# OpenRing_Touch.net
KiCad netlist of a schematic drawn in Altium Designer
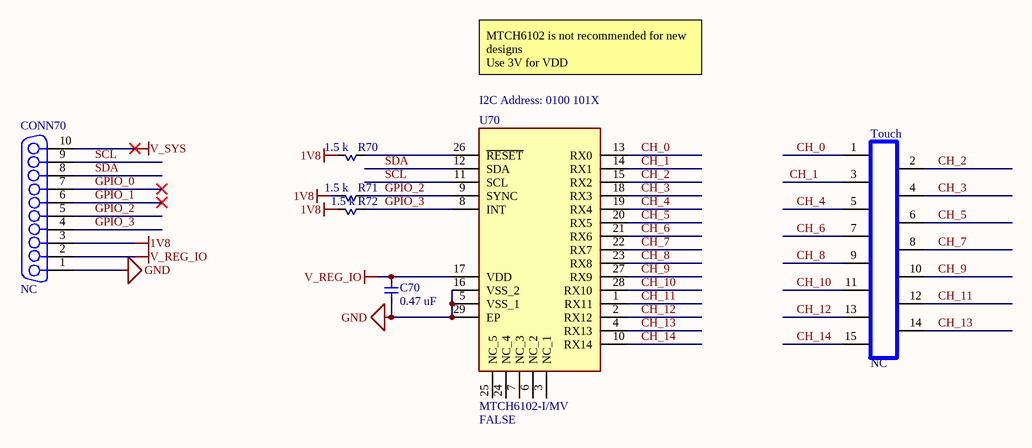
[diagram p0: OpenRing_Touch.SchDoc]

(export (version "E")
  (design (tool "Eeschema 10.0.6"))
  (components
    (comp (ref "C70")
      (value "0.47 uF")
      (footprint "CAPC1005X05N")
      (description "CAP CER 0.47UF 10V X5R 0402")
      (fields
        (field (name "MANUFACTURER") "Murata Electronics North America")
        (field (name "MANUFACTURER PART NUMBER") "GRM155R61A474KE15D")
      )
      (libsource (lib "OpenRingComponents") (part "GRM155R61A474KE15D"))
    )
    (comp (ref "CONN70")
      (value "NC")
      (footprint "51281-1098-PCB")
      (libsource (lib "Connectors") (part "51281-1098-PCB"))
    )
    (comp (ref "R70")
      (value "1.5 k")
      (footprint "RESC1005X04N")
      (description "RES SMD 1.5K OHM 1% 1/10W 0402")
      (fields
        (field (name "MANUFACTURER") "Panasonic Electronic Components")
        (field (name "MANUFACTURER PART NUMBER") "ERJ-2RKF1501X")
      )
      (libsource (lib "OpenRingComponents") (part "ERJ-2RKF1501X"))
    )
    (comp (ref "R71")
      (value "1.5 k")
      (footprint "RESC1005X04N")
      (description "RES SMD 1.5K OHM 1% 1/10W 0402")
      (fields
        (field (name "MANUFACTURER") "Panasonic Electronic Components")
        (field (name "MANUFACTURER PART NUMBER") "ERJ-2RKF1501X")
      )
      (libsource (lib "OpenRingComponents") (part "ERJ-2RKF1501X"))
    )
    (comp (ref "R72")
      (value "1.5 k")
      (footprint "RESC1005X04N")
      (description "RES SMD 1.5K OHM 1% 1/10W 0402")
      (fields
        (field (name "MANUFACTURER") "Panasonic Electronic Components")
        (field (name "MANUFACTURER PART NUMBER") "ERJ-2RKF1501X")
      )
      (libsource (lib "OpenRingComponents") (part "ERJ-2RKF1501X"))
    )
    (comp (ref "Touch")
      (value "NC")
      (footprint "Touch-15Ch-Linear")
      (libsource (lib "OpenRingComponents") (part "Touch-15Ch-Linear"))
    )
    (comp (ref "U70")
      (value "MTCH6102-I/MV")
      (footprint "QFN40P400X400X55_HS-29N")
      (description "Capacitive Touch Screen Automotive 28-Pin UQFN EP Tube")
      (fields (field (name "MANUFACTURER") "Microchip") (field (name "CHECKED") "FALSE"))
      (libsource (lib "OpenRingComponents") (part "MTCH6102-I/MV"))
    )
  )
  (nets
    (net (code "1") (name "/CH_0") (class "Default")
      (node (ref "Touch") (pin "1") (pinfunction "1_1") (pintype "passive"))
      (node (ref "U70") (pin "13") (pinfunction "RX0_13") (pintype "passive"))
    )
    (net (code "2") (name "/CH_1") (class "Default")
      (node (ref "Touch") (pin "3") (pinfunction "3_3") (pintype "passive"))
      (node (ref "U70") (pin "14") (pinfunction "RX1_14") (pintype "passive"))
    )
    (net (code "3") (name "/CH_2") (class "Default")
      (node (ref "Touch") (pin "2") (pinfunction "2_2") (pintype "passive"))
      (node (ref "U70") (pin "15") (pinfunction "RX2_15") (pintype "passive"))
    )
    (net (code "4") (name "/CH_3") (class "Default")
      (node (ref "Touch") (pin "4") (pinfunction "4_4") (pintype "passive"))
      (node (ref "U70") (pin "18") (pinfunction "RX3_18") (pintype "passive"))
    )
    (net (code "5") (name "/CH_4") (class "Default")
      (node (ref "Touch") (pin "5") (pinfunction "5_5") (pintype "passive"))
      (node (ref "U70") (pin "19") (pinfunction "RX4_19") (pintype "passive"))
    )
    (net (code "6") (name "/CH_5") (class "Default")
      (node (ref "Touch") (pin "6") (pinfunction "6_6") (pintype "passive"))
      (node (ref "U70") (pin "20") (pinfunction "RX5_20") (pintype "passive"))
    )
    (net (code "7") (name "/CH_6") (class "Default")
      (node (ref "Touch") (pin "7") (pinfunction "7_7") (pintype "passive"))
      (node (ref "U70") (pin "21") (pinfunction "RX6_21") (pintype "passive"))
    )
    (net (code "8") (name "/CH_7") (class "Default")
      (node (ref "Touch") (pin "8") (pinfunction "8_8") (pintype "passive"))
      (node (ref "U70") (pin "22") (pinfunction "RX7_22") (pintype "passive"))
    )
    (net (code "9") (name "/CH_8") (class "Default")
      (node (ref "Touch") (pin "9") (pinfunction "9_9") (pintype "passive"))
      (node (ref "U70") (pin "23") (pinfunction "RX8_23") (pintype "passive"))
    )
    (net (code "10") (name "/CH_9") (class "Default")
      (node (ref "Touch") (pin "10") (pinfunction "10_10") (pintype "passive"))
      (node (ref "U70") (pin "27") (pinfunction "RX9_27") (pintype "passive"))
    )
    (net (code "11") (name "/CH_10") (class "Default")
      (node (ref "Touch") (pin "11") (pinfunction "11_11") (pintype "passive"))
      (node (ref "U70") (pin "28") (pinfunction "RX10_28") (pintype "passive"))
    )
    (net (code "12") (name "/CH_11") (class "Default")
      (node (ref "Touch") (pin "12") (pinfunction "12_12") (pintype "passive"))
      (node (ref "U70") (pin "1") (pinfunction "RX11_1") (pintype "passive"))
    )
    (net (code "13") (name "/CH_12") (class "Default")
      (node (ref "Touch") (pin "13") (pinfunction "13_13") (pintype "passive"))
      (node (ref "U70") (pin "2") (pinfunction "RX12_2") (pintype "passive"))
    )
    (net (code "14") (name "/CH_13") (class "Default")
      (node (ref "Touch") (pin "14") (pinfunction "14_14") (pintype "passive"))
      (node (ref "U70") (pin "4") (pinfunction "RX13_4") (pintype "passive"))
    )
    (net (code "15") (name "/CH_14") (class "Default")
      (node (ref "Touch") (pin "15") (pinfunction "15_15") (pintype "passive"))
      (node (ref "U70") (pin "10") (pinfunction "RX14_10") (pintype "passive"))
    )
    (net (code "16") (name "/GPIO_0") (class "Default")
      (node (ref "CONN70") (pin "7") (pinfunction "7_7") (pintype "passive+no_connect"))
    )
    (net (code "17") (name "/GPIO_1") (class "Default")
      (node (ref "CONN70") (pin "6") (pinfunction "6_6") (pintype "passive+no_connect"))
    )
    (net (code "18") (name "/GPIO_2") (class "Default")
      (node (ref "CONN70") (pin "5") (pinfunction "5_5") (pintype "passive"))
      (node (ref "R71") (pin "1") (pinfunction "1_1") (pintype "passive"))
      (node (ref "U70") (pin "9") (pinfunction "SYNC_9") (pintype "passive"))
    )
    (net (code "19") (name "/GPIO_3") (class "Default")
      (node (ref "CONN70") (pin "4") (pinfunction "4_4") (pintype "passive"))
      (node (ref "R72") (pin "1") (pinfunction "1_1") (pintype "passive"))
      (node (ref "U70") (pin "8") (pinfunction "INT_8") (pintype "passive"))
    )
    (net (code "20") (name "/SCL") (class "Default")
      (node (ref "CONN70") (pin "9") (pinfunction "9_9") (pintype "passive"))
      (node (ref "U70") (pin "11") (pinfunction "SCL_11") (pintype "passive"))
    )
    (net (code "21") (name "/SDA") (class "Default")
      (node (ref "CONN70") (pin "8") (pinfunction "8_8") (pintype "passive"))
      (node (ref "U70") (pin "12") (pinfunction "SDA_12") (pintype "passive"))
    )
    (net (code "22") (name "1V8") (class "Default")
      (node (ref "CONN70") (pin "3") (pinfunction "3_3") (pintype "passive"))
      (node (ref "R70") (pin "2") (pinfunction "2_2") (pintype "passive"))
      (node (ref "R71") (pin "2") (pinfunction "2_2") (pintype "passive"))
      (node (ref "R72") (pin "2") (pinfunction "2_2") (pintype "passive"))
    )
    (net (code "23") (name "GND") (class "Default")
      (node (ref "C70") (pin "2") (pinfunction "2_2") (pintype "passive"))
      (node (ref "CONN70") (pin "1") (pinfunction "1_1") (pintype "passive"))
      (node (ref "U70") (pin "16") (pinfunction "VSS_2_16") (pintype "passive"))
      (node (ref "U70") (pin "29") (pinfunction "EP_29") (pintype "passive"))
      (node (ref "U70") (pin "5") (pinfunction "VSS_1_5") (pintype "passive"))
    )
    (net (code "24") (name "Net-(U70-~{RESET})") (class "Default")
      (node (ref "R70") (pin "1") (pinfunction "1_1") (pintype "passive"))
      (node (ref "U70") (pin "26") (pinfunction "~{RESET}_26") (pintype "passive"))
    )
    (net (code "25") (name "V_REG_IO") (class "Default")
      (node (ref "C70") (pin "1") (pinfunction "1_1") (pintype "passive"))
      (node (ref "CONN70") (pin "2") (pinfunction "2_2") (pintype "passive"))
      (node (ref "U70") (pin "17") (pinfunction "VDD_17") (pintype "passive"))
    )
    (net (code "26") (name "V_SYS") (class "Default")
      (node (ref "CONN70") (pin "10") (pinfunction "10_10") (pintype "passive"))
    )
    (net (code "27") (name "unconnected-(U70-NC_1-Pad3)") (class "Default")
      (node (ref "U70") (pin "3") (pinfunction "NC_1_3") (pintype "passive"))
    )
    (net (code "28") (name "unconnected-(U70-NC_2-Pad6)") (class "Default")
      (node (ref "U70") (pin "6") (pinfunction "NC_2_6") (pintype "passive"))
    )
    (net (code "29") (name "unconnected-(U70-NC_3-Pad7)") (class "Default")
      (node (ref "U70") (pin "7") (pinfunction "NC_3_7") (pintype "passive"))
    )
    (net (code "30") (name "unconnected-(U70-NC_4-Pad24)") (class "Default")
      (node (ref "U70") (pin "24") (pinfunction "NC_4_24") (pintype "passive"))
    )
    (net (code "31") (name "unconnected-(U70-NC_5-Pad25)") (class "Default")
      (node (ref "U70") (pin "25") (pinfunction "NC_5_25") (pintype "passive"))
    )
  )
)
